# va_sense.net
KiCad netlist of a schematic drawn in EAGLE
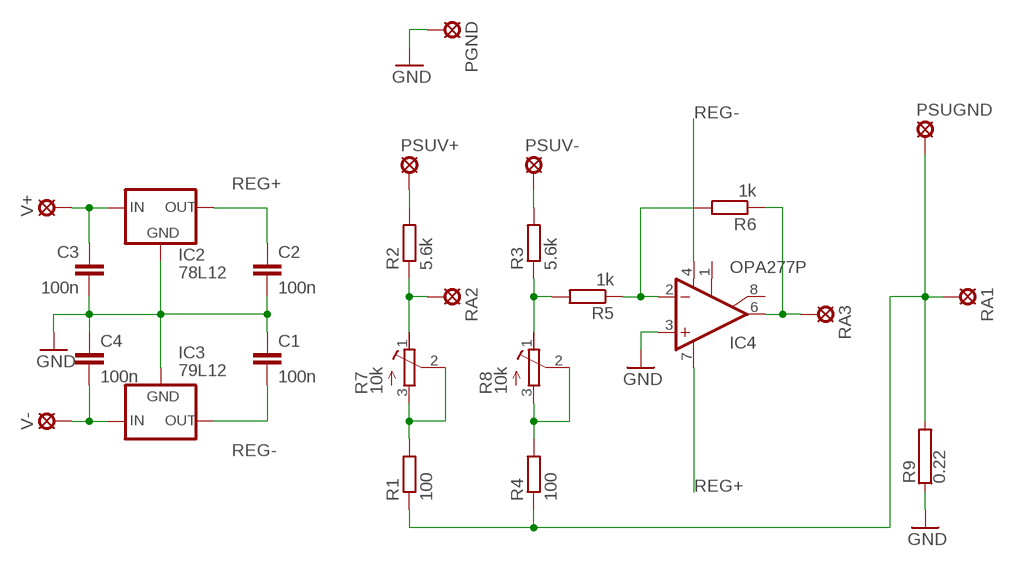
[diagram p0: schematic, sheet 1]

(export (version "E")
  (design (tool "Eeschema 10.0.6"))
  (components
    (comp (ref "C1")
      (value "100n")
      (footprint "eagle-import:C0805K")
      (libsource (lib "eagle-import") (part "C-EUC0805K"))
    )
    (comp (ref "C2")
      (value "100n")
      (footprint "eagle-import:C0805K")
      (libsource (lib "eagle-import") (part "C-EUC0805K"))
    )
    (comp (ref "C3")
      (value "100n")
      (footprint "eagle-import:C0805K")
      (libsource (lib "eagle-import") (part "C-EUC0805K"))
    )
    (comp (ref "C4")
      (value "100n")
      (footprint "eagle-import:C0805K")
      (libsource (lib "eagle-import") (part "C-EUC0805K"))
    )
    (comp (ref "IC2")
      (value "78L12")
      (footprint "eagle-import:78LXX")
      (libsource (lib "eagle-import") (part "78LXX"))
    )
    (comp (ref "IC3")
      (value "79L12")
      (footprint "eagle-import:79LXX")
      (libsource (lib "eagle-import") (part "79LXX"))
    )
    (comp (ref "IC4")
      (value "OPA277P")
      (footprint "eagle-import:DIL08")
      (libsource (lib "eagle-import") (part "OPA277P"))
    )
    (comp (ref "PGND")
      (value "SE13")
      (footprint "eagle-import:SE13")
      (libsource (lib "eagle-import") (part "SE13"))
    )
    (comp (ref "PSUGND")
      (value "SE13")
      (footprint "eagle-import:SE13")
      (libsource (lib "eagle-import") (part "SE13"))
    )
    (comp (ref "PSUV+")
      (value "SE13")
      (footprint "eagle-import:SE13")
      (libsource (lib "eagle-import") (part "SE13"))
    )
    (comp (ref "PSUV-")
      (value "SE13")
      (footprint "eagle-import:SE13")
      (libsource (lib "eagle-import") (part "SE13"))
    )
    (comp (ref "R1")
      (value "100")
      (footprint "eagle-import:0207_10")
      (libsource (lib "eagle-import") (part "R-EU_0207/10"))
    )
    (comp (ref "R2")
      (value "5.6k")
      (footprint "eagle-import:0207_10")
      (libsource (lib "eagle-import") (part "R-EU_0207/10"))
    )
    (comp (ref "R3")
      (value "5.6k")
      (footprint "eagle-import:0207_10")
      (libsource (lib "eagle-import") (part "R-EU_0207/10"))
    )
    (comp (ref "R4")
      (value "100")
      (footprint "eagle-import:0207_10")
      (libsource (lib "eagle-import") (part "R-EU_0207/10"))
    )
    (comp (ref "R5")
      (value "1k")
      (footprint "eagle-import:0207_10")
      (libsource (lib "eagle-import") (part "R-EU_0207/10"))
    )
    (comp (ref "R6")
      (value "1k")
      (footprint "eagle-import:0207_10")
      (libsource (lib "eagle-import") (part "R-EU_0207/10"))
    )
    (comp (ref "R7")
      (value "10k")
      (footprint "eagle-import:RTRIM3006P")
      (libsource (lib "eagle-import") (part "R-TRIMM3006P"))
    )
    (comp (ref "R8")
      (value "10k")
      (footprint "eagle-import:RTRIM3006P")
      (libsource (lib "eagle-import") (part "R-TRIMM3006P"))
    )
    (comp (ref "R9")
      (value "0.22")
      (footprint "eagle-import:KH208-8")
      (libsource (lib "eagle-import") (part "RKH208-8"))
    )
    (comp (ref "RA1")
      (value "SE13")
      (footprint "eagle-import:SE13")
      (libsource (lib "eagle-import") (part "SE13"))
    )
    (comp (ref "RA2")
      (value "SE13")
      (footprint "eagle-import:SE13")
      (libsource (lib "eagle-import") (part "SE13"))
    )
    (comp (ref "RA3")
      (value "SE13")
      (footprint "eagle-import:SE13")
      (libsource (lib "eagle-import") (part "SE13"))
    )
    (comp (ref "V+")
      (value "SE13")
      (footprint "eagle-import:SE13")
      (libsource (lib "eagle-import") (part "SE13"))
    )
    (comp (ref "V-")
      (value "SE13")
      (footprint "eagle-import:SE13")
      (libsource (lib "eagle-import") (part "SE13"))
    )
  )
  (nets
    (net (code "1") (name "/REG+") (class "Default")
      (node (ref "C2") (pin "1") (pinfunction "1_1") (pintype "passive"))
      (node (ref "IC2") (pin "OUT") (pinfunction "OUT_OUT") (pintype "passive"))
      (node (ref "IC4") (pin "7") (pinfunction "V+_7") (pintype "power_in"))
    )
    (net (code "2") (name "/REG-") (class "Default")
      (node (ref "C1") (pin "2") (pinfunction "2_2") (pintype "passive"))
      (node (ref "IC3") (pin "OUT") (pinfunction "OUT_OUT") (pintype "passive"))
      (node (ref "IC4") (pin "4") (pinfunction "V-_4") (pintype "power_in"))
    )
    (net (code "3") (name "GND") (class "Default")
      (node (ref "C1") (pin "1") (pinfunction "1_1") (pintype "passive"))
      (node (ref "C2") (pin "2") (pinfunction "2_2") (pintype "passive"))
      (node (ref "C3") (pin "2") (pinfunction "2_2") (pintype "passive"))
      (node (ref "C4") (pin "1") (pinfunction "1_1") (pintype "passive"))
      (node (ref "IC2") (pin "GND") (pinfunction "GND_GND") (pintype "input"))
      (node (ref "IC3") (pin "GND") (pinfunction "GND_GND") (pintype "input"))
      (node (ref "IC4") (pin "3") (pinfunction "+IN_3") (pintype "input"))
      (node (ref "PGND") (pin "MP") (pinfunction "MP_MP") (pintype "passive"))
      (node (ref "R9") (pin "1") (pinfunction "1_1") (pintype "passive"))
    )
    (net (code "4") (name "Net-(C3-Pad1)") (class "Default")
      (node (ref "C3") (pin "1") (pinfunction "1_1") (pintype "passive"))
      (node (ref "IC2") (pin "IN") (pinfunction "IN_IN") (pintype "input"))
      (node (ref "V+") (pin "MP") (pinfunction "MP_MP") (pintype "passive"))
    )
    (net (code "5") (name "Net-(C4-Pad2)") (class "Default")
      (node (ref "C4") (pin "2") (pinfunction "2_2") (pintype "passive"))
      (node (ref "IC3") (pin "IN") (pinfunction "IN_IN") (pintype "input"))
      (node (ref "V-") (pin "MP") (pinfunction "MP_MP") (pintype "passive"))
    )
    (net (code "6") (name "Net-(IC4--IN)") (class "Default")
      (node (ref "IC4") (pin "2") (pinfunction "-IN_2") (pintype "input"))
      (node (ref "R5") (pin "1") (pinfunction "1_1") (pintype "passive"))
      (node (ref "R6") (pin "2") (pinfunction "2_2") (pintype "passive"))
    )
    (net (code "7") (name "Net-(IC4-OUT)") (class "Default")
      (node (ref "IC4") (pin "6") (pinfunction "OUT_6") (pintype "output"))
      (node (ref "R6") (pin "1") (pinfunction "1_1") (pintype "passive"))
      (node (ref "RA3") (pin "MP") (pinfunction "MP_MP") (pintype "passive"))
    )
    (net (code "8") (name "Net-(PSUGND-PadMP)") (class "Default")
      (node (ref "PSUGND") (pin "MP") (pinfunction "MP_MP") (pintype "passive"))
      (node (ref "R1") (pin "1") (pinfunction "1_1") (pintype "passive"))
      (node (ref "R4") (pin "1") (pinfunction "1_1") (pintype "passive"))
      (node (ref "R9") (pin "2") (pinfunction "2_2") (pintype "passive"))
      (node (ref "RA1") (pin "MP") (pinfunction "MP_MP") (pintype "passive"))
    )
    (net (code "9") (name "Net-(PSUV+-PadMP)") (class "Default")
      (node (ref "PSUV+") (pin "MP") (pinfunction "MP_MP") (pintype "passive"))
      (node (ref "R2") (pin "2") (pinfunction "2_2") (pintype "passive"))
    )
    (net (code "10") (name "Net-(PSUV--PadMP)") (class "Default")
      (node (ref "PSUV-") (pin "MP") (pinfunction "MP_MP") (pintype "passive"))
      (node (ref "R3") (pin "2") (pinfunction "2_2") (pintype "passive"))
    )
    (net (code "11") (name "Net-(R7-A)") (class "Default")
      (node (ref "R2") (pin "1") (pinfunction "1_1") (pintype "passive"))
      (node (ref "R7") (pin "1") (pinfunction "A_1") (pintype "passive"))
      (node (ref "RA2") (pin "MP") (pinfunction "MP_MP") (pintype "passive"))
    )
    (net (code "12") (name "Net-(R7-E)") (class "Default")
      (node (ref "R1") (pin "2") (pinfunction "2_2") (pintype "passive"))
      (node (ref "R7") (pin "2") (pinfunction "S_2") (pintype "passive"))
      (node (ref "R7") (pin "3") (pinfunction "E_3") (pintype "passive"))
    )
    (net (code "13") (name "Net-(R8-A)") (class "Default")
      (node (ref "R3") (pin "1") (pinfunction "1_1") (pintype "passive"))
      (node (ref "R5") (pin "2") (pinfunction "2_2") (pintype "passive"))
      (node (ref "R8") (pin "1") (pinfunction "A_1") (pintype "passive"))
    )
    (net (code "14") (name "Net-(R8-E)") (class "Default")
      (node (ref "R4") (pin "2") (pinfunction "2_2") (pintype "passive"))
      (node (ref "R8") (pin "2") (pinfunction "S_2") (pintype "passive"))
      (node (ref "R8") (pin "3") (pinfunction "E_3") (pintype "passive"))
    )
    (net (code "15") (name "unconnected-(IC4-CMP1-Pad1)") (class "Default")
      (node (ref "IC4") (pin "1") (pinfunction "CMP1_1") (pintype "passive"))
    )
    (net (code "16") (name "unconnected-(IC4-CMP2-Pad8)") (class "Default")
      (node (ref "IC4") (pin "8") (pinfunction "CMP2_8") (pintype "passive"))
    )
  )
)
